# JTAG_Passthrough.net
KiCad netlist of a schematic drawn in EAGLE
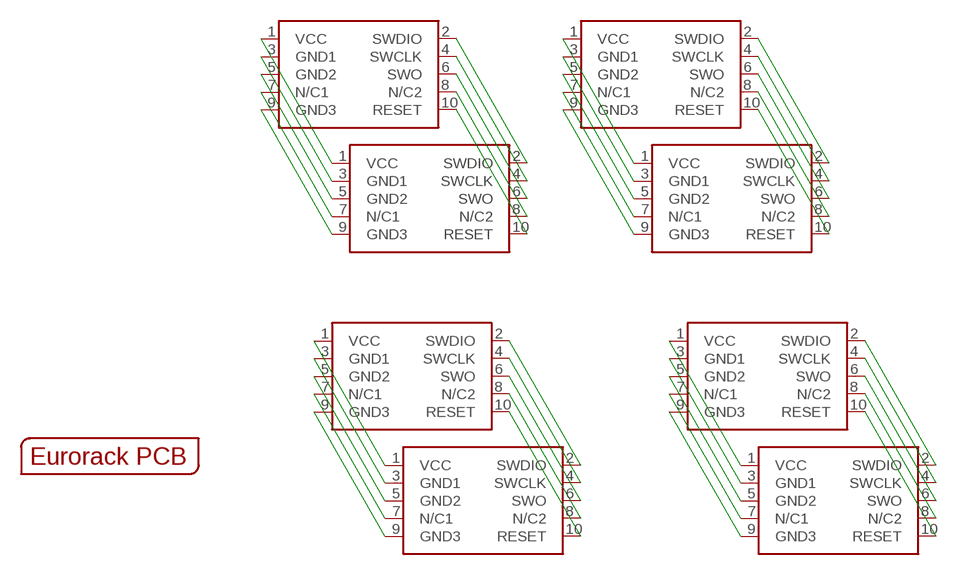
[diagram p0: schematic, sheet 1]

(export (version "E")
  (design (tool "Eeschema 10.0.6"))
  (components
    (comp (ref "SWD1")
      (value "CORTEX_SWD")
      (footprint "eagle-import:M50-3600542")
      (libsource (lib "eagle-import") (part "CORTEX_SWD"))
    )
    (comp (ref "SWD2")
      (value "CORTEX_SWDVERT_HOLE")
      (footprint "eagle-import:SWD_VERTICAL_WITHHOLE")
      (libsource (lib "eagle-import") (part "CORTEX_SWDVERT_HOLE"))
    )
    (comp (ref "SWD3")
      (value "CORTEX_SWD")
      (footprint "eagle-import:M50-3600542")
      (libsource (lib "eagle-import") (part "CORTEX_SWD"))
    )
    (comp (ref "SWD4")
      (value "CORTEX_SWDVERT_HOLE")
      (footprint "eagle-import:SWD_VERTICAL_WITHHOLE")
      (libsource (lib "eagle-import") (part "CORTEX_SWDVERT_HOLE"))
    )
    (comp (ref "SWD5")
      (value "CORTEX_SWD")
      (footprint "eagle-import:M50-3600542")
      (libsource (lib "eagle-import") (part "CORTEX_SWD"))
    )
    (comp (ref "SWD6")
      (value "CORTEX_SWDVERT_HOLE")
      (footprint "eagle-import:SWD_VERTICAL_WITHHOLE")
      (libsource (lib "eagle-import") (part "CORTEX_SWDVERT_HOLE"))
    )
    (comp (ref "SWD7")
      (value "CORTEX_SWD")
      (footprint "eagle-import:M50-3600542")
      (libsource (lib "eagle-import") (part "CORTEX_SWD"))
    )
    (comp (ref "SWD8")
      (value "CORTEX_SWDVERT_HOLE")
      (footprint "eagle-import:SWD_VERTICAL_WITHHOLE")
      (libsource (lib "eagle-import") (part "CORTEX_SWDVERT_HOLE"))
    )
    (comp (ref "U$2")
      (value "EURORACK_PCB2HP")
      (footprint "eagle-import:EURORACK2HPPCB")
      (libsource (lib "eagle-import") (part "EURORACK_PCB2HP"))
    )
  )
  (nets
    (net (code "1") (name "Net-(SWD1-GND1)") (class "Default")
      (node (ref "SWD1") (pin "3") (pinfunction "GND1_3") (pintype "bidirectional"))
      (node (ref "SWD2") (pin "3") (pinfunction "GND1_3") (pintype "bidirectional"))
    )
    (net (code "2") (name "Net-(SWD1-GND2)") (class "Default")
      (node (ref "SWD1") (pin "5") (pinfunction "GND2_5") (pintype "bidirectional"))
      (node (ref "SWD2") (pin "5") (pinfunction "GND2_5") (pintype "bidirectional"))
    )
    (net (code "3") (name "Net-(SWD1-GND3)") (class "Default")
      (node (ref "SWD1") (pin "9") (pinfunction "GND3_9") (pintype "bidirectional"))
      (node (ref "SWD2") (pin "9") (pinfunction "GND3_9") (pintype "bidirectional"))
    )
    (net (code "4") (name "Net-(SWD1-N{slash}C1)") (class "Default")
      (node (ref "SWD1") (pin "7") (pinfunction "N/C1_7") (pintype "bidirectional"))
      (node (ref "SWD2") (pin "7") (pinfunction "N/C1_7") (pintype "bidirectional"))
    )
    (net (code "5") (name "Net-(SWD1-N{slash}C2)") (class "Default")
      (node (ref "SWD1") (pin "8") (pinfunction "N/C2_8") (pintype "bidirectional"))
      (node (ref "SWD2") (pin "8") (pinfunction "N/C2_8") (pintype "bidirectional"))
    )
    (net (code "6") (name "Net-(SWD1-RESET)") (class "Default")
      (node (ref "SWD1") (pin "10") (pinfunction "RESET_10") (pintype "bidirectional"))
      (node (ref "SWD2") (pin "10") (pinfunction "RESET_10") (pintype "bidirectional"))
    )
    (net (code "7") (name "Net-(SWD1-SWCLK)") (class "Default")
      (node (ref "SWD1") (pin "4") (pinfunction "SWCLK_4") (pintype "bidirectional"))
      (node (ref "SWD2") (pin "4") (pinfunction "SWCLK_4") (pintype "bidirectional"))
    )
    (net (code "8") (name "Net-(SWD1-SWDIO)") (class "Default")
      (node (ref "SWD1") (pin "2") (pinfunction "SWDIO_2") (pintype "bidirectional"))
      (node (ref "SWD2") (pin "2") (pinfunction "SWDIO_2") (pintype "bidirectional"))
    )
    (net (code "9") (name "Net-(SWD1-SWO)") (class "Default")
      (node (ref "SWD1") (pin "6") (pinfunction "SWO_6") (pintype "bidirectional"))
      (node (ref "SWD2") (pin "6") (pinfunction "SWO_6") (pintype "bidirectional"))
    )
    (net (code "10") (name "Net-(SWD1-VCC)") (class "Default")
      (node (ref "SWD1") (pin "1") (pinfunction "VCC_1") (pintype "bidirectional"))
      (node (ref "SWD2") (pin "1") (pinfunction "VCC_1") (pintype "bidirectional"))
    )
    (net (code "11") (name "Net-(SWD3-GND1)") (class "Default")
      (node (ref "SWD3") (pin "3") (pinfunction "GND1_3") (pintype "bidirectional"))
      (node (ref "SWD4") (pin "3") (pinfunction "GND1_3") (pintype "bidirectional"))
    )
    (net (code "12") (name "Net-(SWD3-GND2)") (class "Default")
      (node (ref "SWD3") (pin "5") (pinfunction "GND2_5") (pintype "bidirectional"))
      (node (ref "SWD4") (pin "5") (pinfunction "GND2_5") (pintype "bidirectional"))
    )
    (net (code "13") (name "Net-(SWD3-GND3)") (class "Default")
      (node (ref "SWD3") (pin "9") (pinfunction "GND3_9") (pintype "bidirectional"))
      (node (ref "SWD4") (pin "9") (pinfunction "GND3_9") (pintype "bidirectional"))
    )
    (net (code "14") (name "Net-(SWD3-N{slash}C1)") (class "Default")
      (node (ref "SWD3") (pin "7") (pinfunction "N/C1_7") (pintype "bidirectional"))
      (node (ref "SWD4") (pin "7") (pinfunction "N/C1_7") (pintype "bidirectional"))
    )
    (net (code "15") (name "Net-(SWD3-N{slash}C2)") (class "Default")
      (node (ref "SWD3") (pin "8") (pinfunction "N/C2_8") (pintype "bidirectional"))
      (node (ref "SWD4") (pin "8") (pinfunction "N/C2_8") (pintype "bidirectional"))
    )
    (net (code "16") (name "Net-(SWD3-RESET)") (class "Default")
      (node (ref "SWD3") (pin "10") (pinfunction "RESET_10") (pintype "bidirectional"))
      (node (ref "SWD4") (pin "10") (pinfunction "RESET_10") (pintype "bidirectional"))
    )
    (net (code "17") (name "Net-(SWD3-SWCLK)") (class "Default")
      (node (ref "SWD3") (pin "4") (pinfunction "SWCLK_4") (pintype "bidirectional"))
      (node (ref "SWD4") (pin "4") (pinfunction "SWCLK_4") (pintype "bidirectional"))
    )
    (net (code "18") (name "Net-(SWD3-SWDIO)") (class "Default")
      (node (ref "SWD3") (pin "2") (pinfunction "SWDIO_2") (pintype "bidirectional"))
      (node (ref "SWD4") (pin "2") (pinfunction "SWDIO_2") (pintype "bidirectional"))
    )
    (net (code "19") (name "Net-(SWD3-SWO)") (class "Default")
      (node (ref "SWD3") (pin "6") (pinfunction "SWO_6") (pintype "bidirectional"))
      (node (ref "SWD4") (pin "6") (pinfunction "SWO_6") (pintype "bidirectional"))
    )
    (net (code "20") (name "Net-(SWD3-VCC)") (class "Default")
      (node (ref "SWD3") (pin "1") (pinfunction "VCC_1") (pintype "bidirectional"))
      (node (ref "SWD4") (pin "1") (pinfunction "VCC_1") (pintype "bidirectional"))
    )
    (net (code "21") (name "Net-(SWD5-GND1)") (class "Default")
      (node (ref "SWD5") (pin "3") (pinfunction "GND1_3") (pintype "bidirectional"))
      (node (ref "SWD6") (pin "3") (pinfunction "GND1_3") (pintype "bidirectional"))
    )
    (net (code "22") (name "Net-(SWD5-GND2)") (class "Default")
      (node (ref "SWD5") (pin "5") (pinfunction "GND2_5") (pintype "bidirectional"))
      (node (ref "SWD6") (pin "5") (pinfunction "GND2_5") (pintype "bidirectional"))
    )
    (net (code "23") (name "Net-(SWD5-GND3)") (class "Default")
      (node (ref "SWD5") (pin "9") (pinfunction "GND3_9") (pintype "bidirectional"))
      (node (ref "SWD6") (pin "9") (pinfunction "GND3_9") (pintype "bidirectional"))
    )
    (net (code "24") (name "Net-(SWD5-N{slash}C1)") (class "Default")
      (node (ref "SWD5") (pin "7") (pinfunction "N/C1_7") (pintype "bidirectional"))
      (node (ref "SWD6") (pin "7") (pinfunction "N/C1_7") (pintype "bidirectional"))
    )
    (net (code "25") (name "Net-(SWD5-N{slash}C2)") (class "Default")
      (node (ref "SWD5") (pin "8") (pinfunction "N/C2_8") (pintype "bidirectional"))
      (node (ref "SWD6") (pin "8") (pinfunction "N/C2_8") (pintype "bidirectional"))
    )
    (net (code "26") (name "Net-(SWD5-RESET)") (class "Default")
      (node (ref "SWD5") (pin "10") (pinfunction "RESET_10") (pintype "bidirectional"))
      (node (ref "SWD6") (pin "10") (pinfunction "RESET_10") (pintype "bidirectional"))
    )
    (net (code "27") (name "Net-(SWD5-SWCLK)") (class "Default")
      (node (ref "SWD5") (pin "4") (pinfunction "SWCLK_4") (pintype "bidirectional"))
      (node (ref "SWD6") (pin "4") (pinfunction "SWCLK_4") (pintype "bidirectional"))
    )
    (net (code "28") (name "Net-(SWD5-SWDIO)") (class "Default")
      (node (ref "SWD5") (pin "2") (pinfunction "SWDIO_2") (pintype "bidirectional"))
      (node (ref "SWD6") (pin "2") (pinfunction "SWDIO_2") (pintype "bidirectional"))
    )
    (net (code "29") (name "Net-(SWD5-SWO)") (class "Default")
      (node (ref "SWD5") (pin "6") (pinfunction "SWO_6") (pintype "bidirectional"))
      (node (ref "SWD6") (pin "6") (pinfunction "SWO_6") (pintype "bidirectional"))
    )
    (net (code "30") (name "Net-(SWD5-VCC)") (class "Default")
      (node (ref "SWD5") (pin "1") (pinfunction "VCC_1") (pintype "bidirectional"))
      (node (ref "SWD6") (pin "1") (pinfunction "VCC_1") (pintype "bidirectional"))
    )
    (net (code "31") (name "Net-(SWD7-GND1)") (class "Default")
      (node (ref "SWD7") (pin "3") (pinfunction "GND1_3") (pintype "bidirectional"))
      (node (ref "SWD8") (pin "3") (pinfunction "GND1_3") (pintype "bidirectional"))
    )
    (net (code "32") (name "Net-(SWD7-GND2)") (class "Default")
      (node (ref "SWD7") (pin "5") (pinfunction "GND2_5") (pintype "bidirectional"))
      (node (ref "SWD8") (pin "5") (pinfunction "GND2_5") (pintype "bidirectional"))
    )
    (net (code "33") (name "Net-(SWD7-GND3)") (class "Default")
      (node (ref "SWD7") (pin "9") (pinfunction "GND3_9") (pintype "bidirectional"))
      (node (ref "SWD8") (pin "9") (pinfunction "GND3_9") (pintype "bidirectional"))
    )
    (net (code "34") (name "Net-(SWD7-N{slash}C1)") (class "Default")
      (node (ref "SWD7") (pin "7") (pinfunction "N/C1_7") (pintype "bidirectional"))
      (node (ref "SWD8") (pin "7") (pinfunction "N/C1_7") (pintype "bidirectional"))
    )
    (net (code "35") (name "Net-(SWD7-N{slash}C2)") (class "Default")
      (node (ref "SWD7") (pin "8") (pinfunction "N/C2_8") (pintype "bidirectional"))
      (node (ref "SWD8") (pin "8") (pinfunction "N/C2_8") (pintype "bidirectional"))
    )
    (net (code "36") (name "Net-(SWD7-RESET)") (class "Default")
      (node (ref "SWD7") (pin "10") (pinfunction "RESET_10") (pintype "bidirectional"))
      (node (ref "SWD8") (pin "10") (pinfunction "RESET_10") (pintype "bidirectional"))
    )
    (net (code "37") (name "Net-(SWD7-SWCLK)") (class "Default")
      (node (ref "SWD7") (pin "4") (pinfunction "SWCLK_4") (pintype "bidirectional"))
      (node (ref "SWD8") (pin "4") (pinfunction "SWCLK_4") (pintype "bidirectional"))
    )
    (net (code "38") (name "Net-(SWD7-SWDIO)") (class "Default")
      (node (ref "SWD7") (pin "2") (pinfunction "SWDIO_2") (pintype "bidirectional"))
      (node (ref "SWD8") (pin "2") (pinfunction "SWDIO_2") (pintype "bidirectional"))
    )
    (net (code "39") (name "Net-(SWD7-SWO)") (class "Default")
      (node (ref "SWD7") (pin "6") (pinfunction "SWO_6") (pintype "bidirectional"))
      (node (ref "SWD8") (pin "6") (pinfunction "SWO_6") (pintype "bidirectional"))
    )
    (net (code "40") (name "Net-(SWD7-VCC)") (class "Default")
      (node (ref "SWD7") (pin "1") (pinfunction "VCC_1") (pintype "bidirectional"))
      (node (ref "SWD8") (pin "1") (pinfunction "VCC_1") (pintype "bidirectional"))
    )
  )
)
